# Motor_Controller.net
KiCad netlist of a schematic drawn in EAGLE
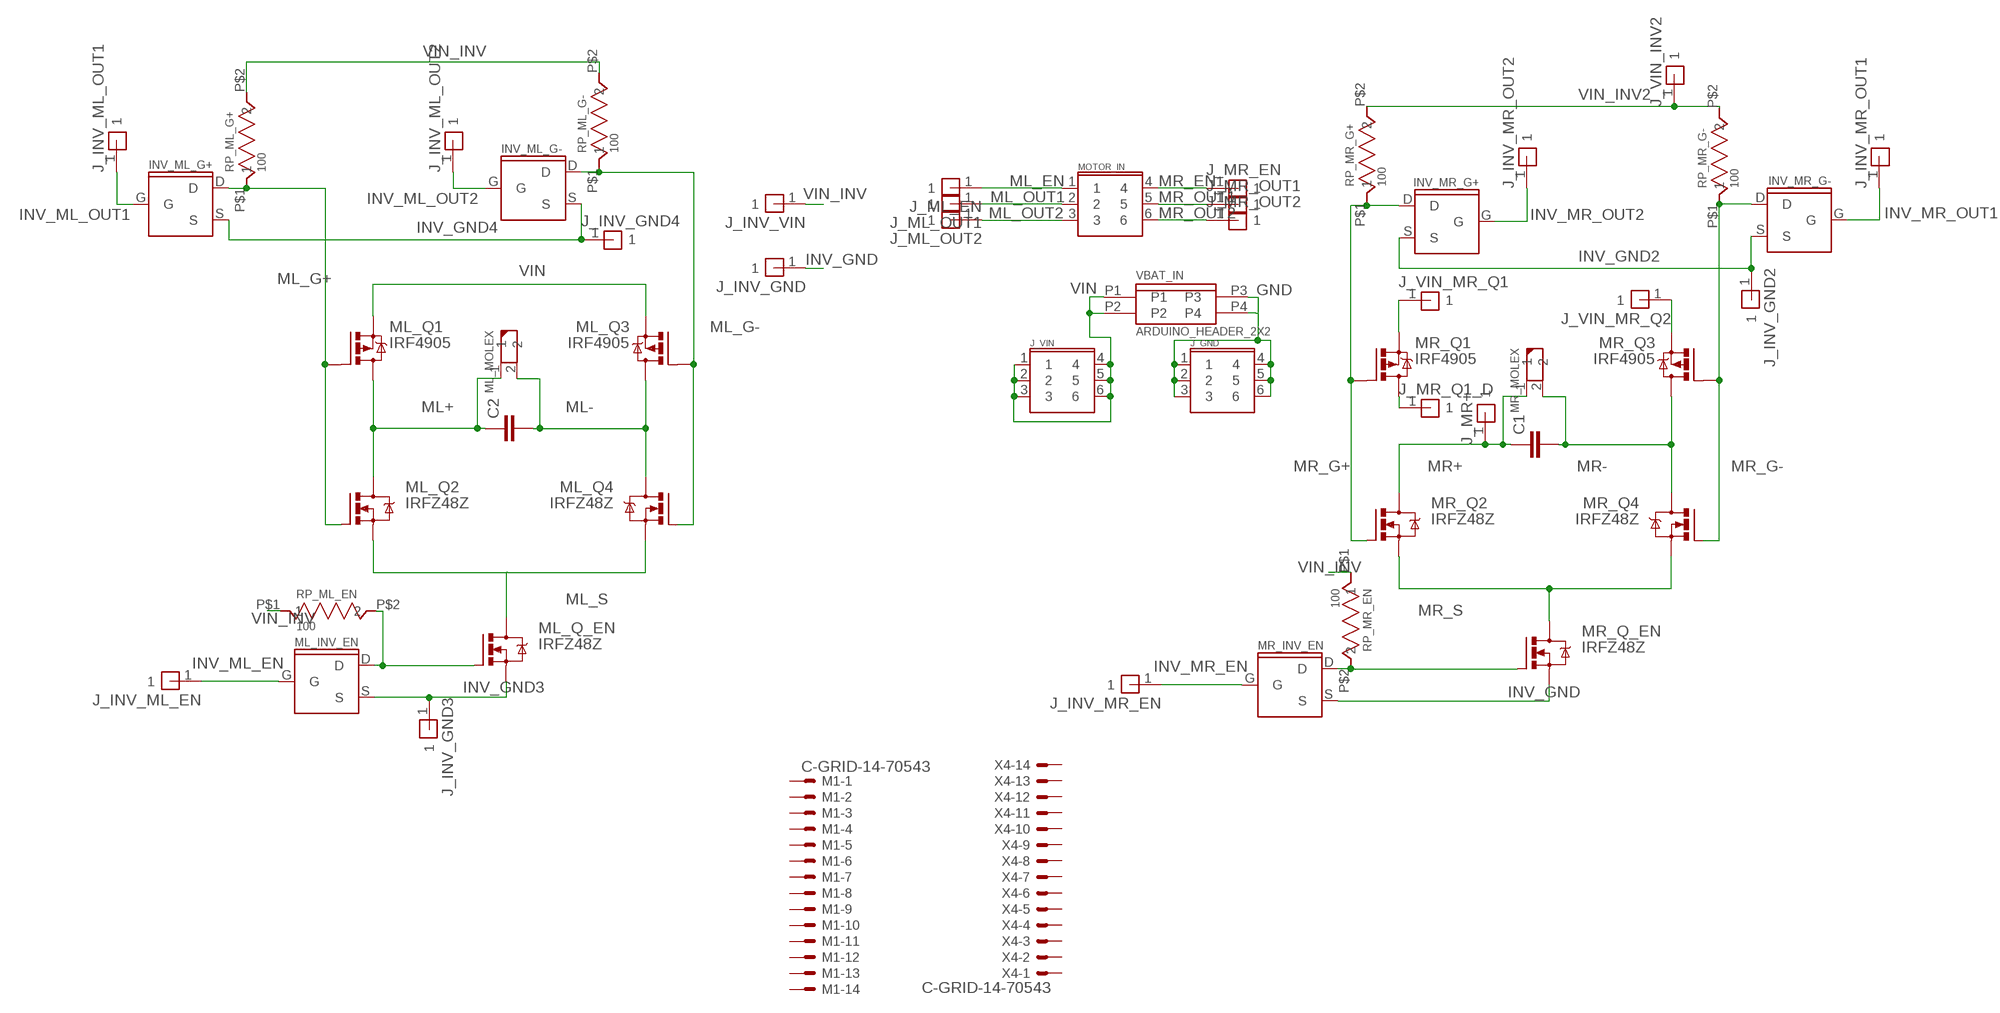
[diagram p0: schematic, sheet 1]

(export (version "E")
  (design (tool "Eeschema 10.0.6"))
  (components
    (comp (ref "C1")
      (value "C5/3")
      (footprint "eagle-import:C5B3")
      (libsource (lib "eagle-import") (part "C5/3"))
    )
    (comp (ref "C2")
      (value "C5/3")
      (footprint "eagle-import:C5B3")
      (libsource (lib "eagle-import") (part "C5/3"))
    )
    (comp (ref "INV_ML_G+")
      (value "2N7000")
      (footprint "eagle-import:TO-92")
      (libsource (lib "eagle-import") (part "2N7000"))
    )
    (comp (ref "INV_ML_G-")
      (value "2N7000")
      (footprint "eagle-import:TO-92")
      (libsource (lib "eagle-import") (part "2N7000"))
    )
    (comp (ref "INV_MR_G+")
      (value "2N7000")
      (footprint "eagle-import:TO-92")
      (libsource (lib "eagle-import") (part "2N7000"))
    )
    (comp (ref "INV_MR_G-")
      (value "2N7000")
      (footprint "eagle-import:TO-92")
      (libsource (lib "eagle-import") (part "2N7000"))
    )
    (comp (ref "J_GND")
      (value "ARDUINO_HEADER_3X2")
      (footprint "eagle-import:ARDUINO_HEADER_3X2")
      (libsource (lib "eagle-import") (part "ARDUINO_HEADER_3X2"))
    )
    (comp (ref "J_INV_GND")
      (value "ARDUINO_HEADER_1X1_OCTAGON")
      (footprint "eagle-import:ARDUINO_HEADER_1X1_OCTAGON")
      (libsource (lib "eagle-import") (part "ARDUINO_HEADER_1X1_OCTAGON"))
    )
    (comp (ref "J_INV_GND2")
      (value "ARDUINO_HEADER_1X1_OCTAGON")
      (footprint "eagle-import:ARDUINO_HEADER_1X1_OCTAGON")
      (libsource (lib "eagle-import") (part "ARDUINO_HEADER_1X1_OCTAGON"))
    )
    (comp (ref "J_INV_GND3")
      (value "ARDUINO_HEADER_1X1_OCTAGON")
      (footprint "eagle-import:ARDUINO_HEADER_1X1_OCTAGON")
      (libsource (lib "eagle-import") (part "ARDUINO_HEADER_1X1_OCTAGON"))
    )
    (comp (ref "J_INV_GND4")
      (value "ARDUINO_HEADER_1X1_OCTAGON")
      (footprint "eagle-import:ARDUINO_HEADER_1X1_OCTAGON")
      (libsource (lib "eagle-import") (part "ARDUINO_HEADER_1X1_OCTAGON"))
    )
    (comp (ref "J_INV_ML_EN")
      (value "ARDUINO_HEADER_1X1_OCTAGON")
      (footprint "eagle-import:ARDUINO_HEADER_1X1_OCTAGON")
      (libsource (lib "eagle-import") (part "ARDUINO_HEADER_1X1_OCTAGON"))
    )
    (comp (ref "J_INV_ML_OUT1")
      (value "ARDUINO_HEADER_1X1_OCTAGON")
      (footprint "eagle-import:ARDUINO_HEADER_1X1_OCTAGON")
      (libsource (lib "eagle-import") (part "ARDUINO_HEADER_1X1_OCTAGON"))
    )
    (comp (ref "J_INV_ML_OUT2")
      (value "ARDUINO_HEADER_1X1_OCTAGON")
      (footprint "eagle-import:ARDUINO_HEADER_1X1_OCTAGON")
      (libsource (lib "eagle-import") (part "ARDUINO_HEADER_1X1_OCTAGON"))
    )
    (comp (ref "J_INV_MR_EN")
      (value "ARDUINO_HEADER_1X1_OCTAGON")
      (footprint "eagle-import:ARDUINO_HEADER_1X1_OCTAGON")
      (libsource (lib "eagle-import") (part "ARDUINO_HEADER_1X1_OCTAGON"))
    )
    (comp (ref "J_INV_MR_OUT1")
      (value "ARDUINO_HEADER_1X1_OCTAGON")
      (footprint "eagle-import:ARDUINO_HEADER_1X1_OCTAGON")
      (libsource (lib "eagle-import") (part "ARDUINO_HEADER_1X1_OCTAGON"))
    )
    (comp (ref "J_INV_MR_OUT2")
      (value "ARDUINO_HEADER_1X1_OCTAGON")
      (footprint "eagle-import:ARDUINO_HEADER_1X1_OCTAGON")
      (libsource (lib "eagle-import") (part "ARDUINO_HEADER_1X1_OCTAGON"))
    )
    (comp (ref "J_INV_VIN")
      (value "ARDUINO_HEADER_1X1_OCTAGON")
      (footprint "eagle-import:ARDUINO_HEADER_1X1_OCTAGON")
      (libsource (lib "eagle-import") (part "ARDUINO_HEADER_1X1_OCTAGON"))
    )
    (comp (ref "J_ML_EN")
      (value "ARDUINO_HEADER_1X1_OCTAGON")
      (footprint "eagle-import:ARDUINO_HEADER_1X1_OCTAGON")
      (libsource (lib "eagle-import") (part "ARDUINO_HEADER_1X1_OCTAGON"))
    )
    (comp (ref "J_ML_OUT1")
      (value "ARDUINO_HEADER_1X1_OCTAGON")
      (footprint "eagle-import:ARDUINO_HEADER_1X1_OCTAGON")
      (libsource (lib "eagle-import") (part "ARDUINO_HEADER_1X1_OCTAGON"))
    )
    (comp (ref "J_ML_OUT2")
      (value "ARDUINO_HEADER_1X1_OCTAGON")
      (footprint "eagle-import:ARDUINO_HEADER_1X1_OCTAGON")
      (libsource (lib "eagle-import") (part "ARDUINO_HEADER_1X1_OCTAGON"))
    )
    (comp (ref "J_MR+")
      (value "ARDUINO_HEADER_1X1_OCTAGON")
      (footprint "eagle-import:ARDUINO_HEADER_1X1_OCTAGON")
      (libsource (lib "eagle-import") (part "ARDUINO_HEADER_1X1_OCTAGON"))
    )
    (comp (ref "J_MR_EN")
      (value "ARDUINO_HEADER_1X1_OCTAGON")
      (footprint "eagle-import:ARDUINO_HEADER_1X1_OCTAGON")
      (libsource (lib "eagle-import") (part "ARDUINO_HEADER_1X1_OCTAGON"))
    )
    (comp (ref "J_MR_OUT1")
      (value "ARDUINO_HEADER_1X1_OCTAGON")
      (footprint "eagle-import:ARDUINO_HEADER_1X1_OCTAGON")
      (libsource (lib "eagle-import") (part "ARDUINO_HEADER_1X1_OCTAGON"))
    )
    (comp (ref "J_MR_OUT2")
      (value "ARDUINO_HEADER_1X1_OCTAGON")
      (footprint "eagle-import:ARDUINO_HEADER_1X1_OCTAGON")
      (libsource (lib "eagle-import") (part "ARDUINO_HEADER_1X1_OCTAGON"))
    )
    (comp (ref "J_MR_Q1_D")
      (value "ARDUINO_HEADER_1X1_OCTAGON")
      (footprint "eagle-import:ARDUINO_HEADER_1X1_OCTAGON")
      (libsource (lib "eagle-import") (part "ARDUINO_HEADER_1X1_OCTAGON"))
    )
    (comp (ref "J_VIN")
      (value "ARDUINO_HEADER_3X2")
      (footprint "eagle-import:ARDUINO_HEADER_3X2")
      (libsource (lib "eagle-import") (part "ARDUINO_HEADER_3X2"))
    )
    (comp (ref "J_VIN_INV2")
      (value "ARDUINO_HEADER_1X1_OCTAGON")
      (footprint "eagle-import:ARDUINO_HEADER_1X1_OCTAGON")
      (libsource (lib "eagle-import") (part "ARDUINO_HEADER_1X1_OCTAGON"))
    )
    (comp (ref "J_VIN_MR_Q1")
      (value "ARDUINO_HEADER_1X1_OCTAGON")
      (footprint "eagle-import:ARDUINO_HEADER_1X1_OCTAGON")
      (libsource (lib "eagle-import") (part "ARDUINO_HEADER_1X1_OCTAGON"))
    )
    (comp (ref "J_VIN_MR_Q2")
      (value "ARDUINO_HEADER_1X1_OCTAGON")
      (footprint "eagle-import:ARDUINO_HEADER_1X1_OCTAGON")
      (libsource (lib "eagle-import") (part "ARDUINO_HEADER_1X1_OCTAGON"))
    )
    (comp (ref "M1")
      (value "C-GRID-14-70543")
      (footprint "eagle-import:70543-14")
      (libsource (lib "eagle-import") (part "C-GRID-14-70543"))
    )
    (comp (ref "ML_INV_EN")
      (value "2N7000")
      (footprint "eagle-import:TO-92")
      (libsource (lib "eagle-import") (part "2N7000"))
    )
    (comp (ref "ML_MOLEX")
      (value "MOLEX_2_PIN")
      (footprint "eagle-import:MOLEX_2_PIN")
      (libsource (lib "eagle-import") (part "MOLEX_2_PIN"))
    )
    (comp (ref "ML_Q1")
      (value "IRF4905")
      (footprint "eagle-import:TO220BH")
      (libsource (lib "eagle-import") (part "IRF4905"))
    )
    (comp (ref "ML_Q2")
      (value "IRFZ48Z")
      (footprint "eagle-import:TO220BH")
      (libsource (lib "eagle-import") (part "IRFZ48Z"))
    )
    (comp (ref "ML_Q3")
      (value "IRF4905")
      (footprint "eagle-import:TO220BH")
      (libsource (lib "eagle-import") (part "IRF4905"))
    )
    (comp (ref "ML_Q4")
      (value "IRFZ48Z")
      (footprint "eagle-import:TO220BH")
      (libsource (lib "eagle-import") (part "IRFZ48Z"))
    )
    (comp (ref "ML_Q_EN")
      (value "IRFZ48Z")
      (footprint "eagle-import:TO220BH")
      (libsource (lib "eagle-import") (part "IRFZ48Z"))
    )
    (comp (ref "MOTOR_IN")
      (value "ARDUINO_HEADER_3X2")
      (footprint "eagle-import:ARDUINO_HEADER_3X2")
      (libsource (lib "eagle-import") (part "ARDUINO_HEADER_3X2"))
    )
    (comp (ref "MR_INV_EN")
      (value "2N7000")
      (footprint "eagle-import:TO-92")
      (libsource (lib "eagle-import") (part "2N7000"))
    )
    (comp (ref "MR_MOLEX")
      (value "MOLEX_2_PIN")
      (footprint "eagle-import:MOLEX_2_PIN")
      (libsource (lib "eagle-import") (part "MOLEX_2_PIN"))
    )
    (comp (ref "MR_Q1")
      (value "IRF4905")
      (footprint "eagle-import:TO220BH")
      (libsource (lib "eagle-import") (part "IRF4905"))
    )
    (comp (ref "MR_Q2")
      (value "IRFZ48Z")
      (footprint "eagle-import:TO220BH")
      (libsource (lib "eagle-import") (part "IRFZ48Z"))
    )
    (comp (ref "MR_Q3")
      (value "IRF4905")
      (footprint "eagle-import:TO220BH")
      (libsource (lib "eagle-import") (part "IRF4905"))
    )
    (comp (ref "MR_Q4")
      (value "IRFZ48Z")
      (footprint "eagle-import:TO220BH")
      (libsource (lib "eagle-import") (part "IRFZ48Z"))
    )
    (comp (ref "MR_Q_EN")
      (value "IRFZ48Z")
      (footprint "eagle-import:TO220BH")
      (libsource (lib "eagle-import") (part "IRFZ48Z"))
    )
    (comp (ref "RP_ML_EN")
      (value "100")
      (footprint "eagle-import:RESISTOR_THROUGH_8MM")
      (libsource (lib "eagle-import") (part "RESISTOR_THROUGH_8MM"))
    )
    (comp (ref "RP_ML_G+")
      (value "100")
      (footprint "eagle-import:RESISTOR_THROUGH_8MM")
      (libsource (lib "eagle-import") (part "RESISTOR_THROUGH_8MM"))
    )
    (comp (ref "RP_ML_G-")
      (value "100")
      (footprint "eagle-import:RESISTOR_THROUGH_8MM")
      (libsource (lib "eagle-import") (part "RESISTOR_THROUGH_8MM"))
    )
    (comp (ref "RP_MR_EN")
      (value "100")
      (footprint "eagle-import:RESISTOR_THROUGH_8MM")
      (libsource (lib "eagle-import") (part "RESISTOR_THROUGH_8MM"))
    )
    (comp (ref "RP_MR_G+")
      (value "100")
      (footprint "eagle-import:RESISTOR_THROUGH_8MM")
      (libsource (lib "eagle-import") (part "RESISTOR_THROUGH_8MM"))
    )
    (comp (ref "RP_MR_G-")
      (value "100")
      (footprint "eagle-import:RESISTOR_THROUGH_8MM")
      (libsource (lib "eagle-import") (part "RESISTOR_THROUGH_8MM"))
    )
    (comp (ref "VBAT_IN")
      (value "ARDUINO_HEADER_2X2")
      (footprint "eagle-import:ARDUINO_HEADER_2X2")
      (libsource (lib "eagle-import") (part "ARDUINO_HEADER_2X2"))
    )
    (comp (ref "X4")
      (value "C-GRID-14-70543")
      (footprint "eagle-import:70543-14")
      (libsource (lib "eagle-import") (part "C-GRID-14-70543"))
    )
  )
  (nets
    (net (code "1") (name "/GND") (class "Default")
      (node (ref "J_GND") (pin "1") (pinfunction "1_1") (pintype "bidirectional"))
      (node (ref "J_GND") (pin "2") (pinfunction "2_2") (pintype "bidirectional"))
      (node (ref "J_GND") (pin "3") (pinfunction "3_3") (pintype "bidirectional"))
      (node (ref "J_GND") (pin "4") (pinfunction "4_4") (pintype "bidirectional"))
      (node (ref "J_GND") (pin "5") (pinfunction "5_5") (pintype "bidirectional"))
      (node (ref "J_GND") (pin "6") (pinfunction "6_6") (pintype "bidirectional"))
      (node (ref "VBAT_IN") (pin "P3") (pinfunction "P3_P3") (pintype "bidirectional"))
      (node (ref "VBAT_IN") (pin "P4") (pinfunction "P4_P4") (pintype "bidirectional"))
    )
    (net (code "2") (name "/INV_GND") (class "Default")
      (node (ref "J_INV_GND") (pin "1") (pinfunction "1_1") (pintype "bidirectional"))
      (node (ref "MR_INV_EN") (pin "S") (pinfunction "S_S") (pintype "bidirectional"))
      (node (ref "MR_Q_EN") (pin "S") (pinfunction "S_S") (pintype "passive"))
    )
    (net (code "3") (name "/INV_GND2") (class "Default")
      (node (ref "INV_MR_G+") (pin "S") (pinfunction "S_S") (pintype "bidirectional"))
      (node (ref "INV_MR_G-") (pin "S") (pinfunction "S_S") (pintype "bidirectional"))
      (node (ref "J_INV_GND2") (pin "1") (pinfunction "1_1") (pintype "bidirectional"))
    )
    (net (code "4") (name "/INV_GND3") (class "Default")
      (node (ref "J_INV_GND3") (pin "1") (pinfunction "1_1") (pintype "bidirectional"))
      (node (ref "ML_INV_EN") (pin "S") (pinfunction "S_S") (pintype "bidirectional"))
      (node (ref "ML_Q_EN") (pin "S") (pinfunction "S_S") (pintype "passive"))
    )
    (net (code "5") (name "/INV_GND4") (class "Default")
      (node (ref "INV_ML_G+") (pin "S") (pinfunction "S_S") (pintype "bidirectional"))
      (node (ref "INV_ML_G-") (pin "S") (pinfunction "S_S") (pintype "bidirectional"))
      (node (ref "J_INV_GND4") (pin "1") (pinfunction "1_1") (pintype "bidirectional"))
    )
    (net (code "6") (name "/INV_ML_EN") (class "Default")
      (node (ref "J_INV_ML_EN") (pin "1") (pinfunction "1_1") (pintype "bidirectional"))
      (node (ref "ML_INV_EN") (pin "G") (pinfunction "G_G") (pintype "bidirectional"))
    )
    (net (code "7") (name "/INV_ML_OUT1") (class "Default")
      (node (ref "INV_ML_G+") (pin "G") (pinfunction "G_G") (pintype "bidirectional"))
      (node (ref "J_INV_ML_OUT1") (pin "1") (pinfunction "1_1") (pintype "bidirectional"))
    )
    (net (code "8") (name "/INV_ML_OUT2") (class "Default")
      (node (ref "INV_ML_G-") (pin "G") (pinfunction "G_G") (pintype "bidirectional"))
      (node (ref "J_INV_ML_OUT2") (pin "1") (pinfunction "1_1") (pintype "bidirectional"))
    )
    (net (code "9") (name "/INV_MR_EN") (class "Default")
      (node (ref "J_INV_MR_EN") (pin "1") (pinfunction "1_1") (pintype "bidirectional"))
      (node (ref "MR_INV_EN") (pin "G") (pinfunction "G_G") (pintype "bidirectional"))
    )
    (net (code "10") (name "/INV_MR_OUT1") (class "Default")
      (node (ref "INV_MR_G-") (pin "G") (pinfunction "G_G") (pintype "bidirectional"))
      (node (ref "J_INV_MR_OUT1") (pin "1") (pinfunction "1_1") (pintype "bidirectional"))
    )
    (net (code "11") (name "/INV_MR_OUT2") (class "Default")
      (node (ref "INV_MR_G+") (pin "G") (pinfunction "G_G") (pintype "bidirectional"))
      (node (ref "J_INV_MR_OUT2") (pin "1") (pinfunction "1_1") (pintype "bidirectional"))
    )
    (net (code "12") (name "/ML+") (class "Default")
      (node (ref "C2") (pin "1") (pinfunction "1_1") (pintype "passive"))
      (node (ref "ML_MOLEX") (pin "1") (pinfunction "1_1") (pintype "bidirectional"))
      (node (ref "ML_Q1") (pin "D") (pinfunction "D_D") (pintype "passive"))
      (node (ref "ML_Q2") (pin "D") (pinfunction "D_D") (pintype "passive"))
    )
    (net (code "13") (name "/ML-") (class "Default")
      (node (ref "C2") (pin "2") (pinfunction "2_2") (pintype "passive"))
      (node (ref "ML_MOLEX") (pin "2") (pinfunction "2_2") (pintype "bidirectional"))
      (node (ref "ML_Q3") (pin "D") (pinfunction "D_D") (pintype "passive"))
      (node (ref "ML_Q4") (pin "D") (pinfunction "D_D") (pintype "passive"))
    )
    (net (code "14") (name "/ML_EN") (class "Default")
      (node (ref "J_ML_EN") (pin "1") (pinfunction "1_1") (pintype "bidirectional"))
      (node (ref "MOTOR_IN") (pin "1") (pinfunction "1_1") (pintype "bidirectional"))
    )
    (net (code "15") (name "/ML_G+") (class "Default")
      (node (ref "INV_ML_G+") (pin "D") (pinfunction "D_D") (pintype "bidirectional"))
      (node (ref "ML_Q1") (pin "G") (pinfunction "G_G") (pintype "passive"))
      (node (ref "ML_Q2") (pin "G") (pinfunction "G_G") (pintype "passive"))
      (node (ref "RP_ML_G+") (pin "P$1") (pinfunction "1_P$1") (pintype "bidirectional"))
    )
    (net (code "16") (name "/ML_G-") (class "Default")
      (node (ref "INV_ML_G-") (pin "D") (pinfunction "D_D") (pintype "bidirectional"))
      (node (ref "ML_Q3") (pin "G") (pinfunction "G_G") (pintype "passive"))
      (node (ref "ML_Q4") (pin "G") (pinfunction "G_G") (pintype "passive"))
      (node (ref "RP_ML_G-") (pin "P$1") (pinfunction "1_P$1") (pintype "bidirectional"))
    )
    (net (code "17") (name "/ML_OUT1") (class "Default")
      (node (ref "J_ML_OUT1") (pin "1") (pinfunction "1_1") (pintype "bidirectional"))
      (node (ref "MOTOR_IN") (pin "2") (pinfunction "2_2") (pintype "bidirectional"))
    )
    (net (code "18") (name "/ML_OUT2") (class "Default")
      (node (ref "J_ML_OUT2") (pin "1") (pinfunction "1_1") (pintype "bidirectional"))
      (node (ref "MOTOR_IN") (pin "3") (pinfunction "3_3") (pintype "bidirectional"))
    )
    (net (code "19") (name "/ML_S") (class "Default")
      (node (ref "ML_Q2") (pin "S") (pinfunction "S_S") (pintype "passive"))
      (node (ref "ML_Q4") (pin "S") (pinfunction "S_S") (pintype "passive"))
      (node (ref "ML_Q_EN") (pin "D") (pinfunction "D_D") (pintype "passive"))
    )
    (net (code "20") (name "/MR+") (class "Default")
      (node (ref "C1") (pin "1") (pinfunction "1_1") (pintype "passive"))
      (node (ref "J_MR+") (pin "1") (pinfunction "1_1") (pintype "bidirectional"))
      (node (ref "MR_MOLEX") (pin "1") (pinfunction "1_1") (pintype "bidirectional"))
      (node (ref "MR_Q2") (pin "D") (pinfunction "D_D") (pintype "passive"))
    )
    (net (code "21") (name "/MR-") (class "Default")
      (node (ref "C1") (pin "2") (pinfunction "2_2") (pintype "passive"))
      (node (ref "MR_MOLEX") (pin "2") (pinfunction "2_2") (pintype "bidirectional"))
      (node (ref "MR_Q3") (pin "D") (pinfunction "D_D") (pintype "passive"))
      (node (ref "MR_Q4") (pin "D") (pinfunction "D_D") (pintype "passive"))
    )
    (net (code "22") (name "/MR_EN") (class "Default")
      (node (ref "J_MR_EN") (pin "1") (pinfunction "1_1") (pintype "bidirectional"))
      (node (ref "MOTOR_IN") (pin "4") (pinfunction "4_4") (pintype "bidirectional"))
    )
    (net (code "23") (name "/MR_G+") (class "Default")
      (node (ref "INV_MR_G+") (pin "D") (pinfunction "D_D") (pintype "bidirectional"))
      (node (ref "MR_Q1") (pin "G") (pinfunction "G_G") (pintype "passive"))
      (node (ref "MR_Q2") (pin "G") (pinfunction "G_G") (pintype "passive"))
      (node (ref "RP_MR_G+") (pin "P$1") (pinfunction "1_P$1") (pintype "bidirectional"))
    )
    (net (code "24") (name "/MR_G-") (class "Default")
      (node (ref "INV_MR_G-") (pin "D") (pinfunction "D_D") (pintype "bidirectional"))
      (node (ref "MR_Q3") (pin "G") (pinfunction "G_G") (pintype "passive"))
      (node (ref "MR_Q4") (pin "G") (pinfunction "G_G") (pintype "passive"))
      (node (ref "RP_MR_G-") (pin "P$1") (pinfunction "1_P$1") (pintype "bidirectional"))
    )
    (net (code "25") (name "/MR_OUT1") (class "Default")
      (node (ref "J_MR_OUT1") (pin "1") (pinfunction "1_1") (pintype "bidirectional"))
      (node (ref "MOTOR_IN") (pin "5") (pinfunction "5_5") (pintype "bidirectional"))
    )
    (net (code "26") (name "/MR_OUT2") (class "Default")
      (node (ref "J_MR_OUT2") (pin "1") (pinfunction "1_1") (pintype "bidirectional"))
      (node (ref "MOTOR_IN") (pin "6") (pinfunction "6_6") (pintype "bidirectional"))
    )
    (net (code "27") (name "/MR_S") (class "Default")
      (node (ref "MR_Q2") (pin "S") (pinfunction "S_S") (pintype "passive"))
      (node (ref "MR_Q4") (pin "S") (pinfunction "S_S") (pintype "passive"))
      (node (ref "MR_Q_EN") (pin "D") (pinfunction "D_D") (pintype "passive"))
    )
    (net (code "28") (name "/VIN") (class "Default")
      (node (ref "J_VIN") (pin "1") (pinfunction "1_1") (pintype "bidirectional"))
      (node (ref "J_VIN") (pin "2") (pinfunction "2_2") (pintype "bidirectional"))
      (node (ref "J_VIN") (pin "3") (pinfunction "3_3") (pintype "bidirectional"))
      (node (ref "J_VIN") (pin "4") (pinfunction "4_4") (pintype "bidirectional"))
      (node (ref "J_VIN") (pin "5") (pinfunction "5_5") (pintype "bidirectional"))
      (node (ref "J_VIN") (pin "6") (pinfunction "6_6") (pintype "bidirectional"))
      (node (ref "ML_Q1") (pin "S") (pinfunction "S_S") (pintype "passive"))
      (node (ref "ML_Q3") (pin "S") (pinfunction "S_S") (pintype "passive"))
      (node (ref "VBAT_IN") (pin "P1") (pinfunction "P1_P1") (pintype "bidirectional"))
      (node (ref "VBAT_IN") (pin "P2") (pinfunction "P2_P2") (pintype "bidirectional"))
    )
    (net (code "29") (name "/VIN_INV") (class "Default")
      (node (ref "J_INV_VIN") (pin "1") (pinfunction "1_1") (pintype "bidirectional"))
      (node (ref "RP_ML_EN") (pin "P$1") (pinfunction "1_P$1") (pintype "bidirectional"))
      (node (ref "RP_ML_G+") (pin "P$2") (pinfunction "2_P$2") (pintype "bidirectional"))
      (node (ref "RP_ML_G-") (pin "P$2") (pinfunction "2_P$2") (pintype "bidirectional"))
      (node (ref "RP_MR_EN") (pin "P$1") (pinfunction "1_P$1") (pintype "bidirectional"))
    )
    (net (code "30") (name "/VIN_INV2") (class "Default")
      (node (ref "J_VIN_INV2") (pin "1") (pinfunction "1_1") (pintype "bidirectional"))
      (node (ref "RP_MR_G+") (pin "P$2") (pinfunction "2_P$2") (pintype "bidirectional"))
      (node (ref "RP_MR_G-") (pin "P$2") (pinfunction "2_P$2") (pintype "bidirectional"))
    )
    (net (code "31") (name "Net-(J_MR_Q1_D-Pad1)") (class "Default")
      (node (ref "J_MR_Q1_D") (pin "1") (pinfunction "1_1") (pintype "bidirectional"))
      (node (ref "MR_Q1") (pin "D") (pinfunction "D_D") (pintype "passive"))
    )
    (net (code "32") (name "Net-(J_VIN_MR_Q1-Pad1)") (class "Default")
      (node (ref "J_VIN_MR_Q1") (pin "1") (pinfunction "1_1") (pintype "bidirectional"))
      (node (ref "MR_Q1") (pin "S") (pinfunction "S_S") (pintype "passive"))
    )
    (net (code "33") (name "Net-(J_VIN_MR_Q2-Pad1)") (class "Default")
      (node (ref "J_VIN_MR_Q2") (pin "1") (pinfunction "1_1") (pintype "bidirectional"))
      (node (ref "MR_Q3") (pin "S") (pinfunction "S_S") (pintype "passive"))
    )
    (net (code "34") (name "Net-(RP_ML_EN-2)") (class "Default")
      (node (ref "ML_INV_EN") (pin "D") (pinfunction "D_D") (pintype "bidirectional"))
      (node (ref "ML_Q_EN") (pin "G") (pinfunction "G_G") (pintype "passive"))
      (node (ref "RP_ML_EN") (pin "P$2") (pinfunction "2_P$2") (pintype "bidirectional"))
    )
    (net (code "35") (name "Net-(RP_MR_EN-2)") (class "Default")
      (node (ref "MR_INV_EN") (pin "D") (pinfunction "D_D") (pintype "bidirectional"))
      (node (ref "MR_Q_EN") (pin "G") (pinfunction "G_G") (pintype "passive"))
      (node (ref "RP_MR_EN") (pin "P$2") (pinfunction "2_P$2") (pintype "bidirectional"))
    )
    (net (code "36") (name "unconnected-(M1A-S-Pad1)") (class "Default")
      (node (ref "M1") (pin "1") (pinfunction "S_1") (pintype "passive"))
    )
    (net (code "37") (name "unconnected-(M1B-S-Pad10)") (class "Default")
      (node (ref "M1") (pin "10") (pinfunction "S_10") (pintype "passive"))
    )
    (net (code "38") (name "unconnected-(M1C-S-Pad11)") (class "Default")
      (node (ref "M1") (pin "11") (pinfunction "S_11") (pintype "passive"))
    )
    (net (code "39") (name "unconnected-(M1D-S-Pad12)") (class "Default")
      (node (ref "M1") (pin "12") (pinfunction "S_12") (pintype "passive"))
    )
    (net (code "40") (name "unconnected-(M1E-S-Pad13)") (class "Default")
      (node (ref "M1") (pin "13") (pinfunction "S_13") (pintype "passive"))
    )
    (net (code "41") (name "unconnected-(M1F-S-Pad14)") (class "Default")
      (node (ref "M1") (pin "14") (pinfunction "S_14") (pintype "passive"))
    )
    (net (code "42") (name "unconnected-(M1G-S-Pad2)") (class "Default")
      (node (ref "M1") (pin "2") (pinfunction "S_2") (pintype "passive"))
    )
    (net (code "43") (name "unconnected-(M1H-S-Pad3)") (class "Default")
      (node (ref "M1") (pin "3") (pinfunction "S_3") (pintype "passive"))
    )
    (net (code "44") (name "unconnected-(M1I-S-Pad4)") (class "Default")
      (node (ref "M1") (pin "4") (pinfunction "S_4") (pintype "passive"))
    )
    (net (code "45") (name "unconnected-(M1J-S-Pad5)") (class "Default")
      (node (ref "M1") (pin "5") (pinfunction "S_5") (pintype "passive"))
    )
    (net (code "46") (name "unconnected-(M1K-S-Pad6)") (class "Default")
      (node (ref "M1") (pin "6") (pinfunction "S_6") (pintype "passive"))
    )
    (net (code "47") (name "unconnected-(M1L-S-Pad7)") (class "Default")
      (node (ref "M1") (pin "7") (pinfunction "S_7") (pintype "passive"))
    )
    (net (code "48") (name "unconnected-(M1M-S-Pad8)") (class "Default")
      (node (ref "M1") (pin "8") (pinfunction "S_8") (pintype "passive"))
    )
    (net (code "49") (name "unconnected-(M1N-S-Pad9)") (class "Default")
      (node (ref "M1") (pin "9") (pinfunction "S_9") (pintype "passive"))
    )
    (net (code "50") (name "unconnected-(X4A-S-Pad1)") (class "Default")
      (node (ref "X4") (pin "1") (pinfunction "S_1") (pintype "passive"))
    )
    (net (code "51") (name "unconnected-(X4B-S-Pad10)") (class "Default")
      (node (ref "X4") (pin "10") (pinfunction "S_10") (pintype "passive"))
    )
    (net (code "52") (name "unconnected-(X4C-S-Pad11)") (class "Default")
      (node (ref "X4") (pin "11") (pinfunction "S_11") (pintype "passive"))
    )
    (net (code "53") (name "unconnected-(X4D-S-Pad12)") (class "Default")
      (node (ref "X4") (pin "12") (pinfunction "S_12") (pintype "passive"))
    )
    (net (code "54") (name "unconnected-(X4E-S-Pad13)") (class "Default")
      (node (ref "X4") (pin "13") (pinfunction "S_13") (pintype "passive"))
    )
    (net (code "55") (name "unconnected-(X4F-S-Pad14)") (class "Default")
      (node (ref "X4") (pin "14") (pinfunction "S_14") (pintype "passive"))
    )
    (net (code "56") (name "unconnected-(X4G-S-Pad2)") (class "Default")
      (node (ref "X4") (pin "2") (pinfunction "S_2") (pintype "passive"))
    )
    (net (code "57") (name "unconnected-(X4H-S-Pad3)") (class "Default")
      (node (ref "X4") (pin "3") (pinfunction "S_3") (pintype "passive"))
    )
    (net (code "58") (name "unconnected-(X4I-S-Pad4)") (class "Default")
      (node (ref "X4") (pin "4") (pinfunction "S_4") (pintype "passive"))
    )
    (net (code "59") (name "unconnected-(X4J-S-Pad5)") (class "Default")
      (node (ref "X4") (pin "5") (pinfunction "S_5") (pintype "passive"))
    )
    (net (code "60") (name "unconnected-(X4K-S-Pad6)") (class "Default")
      (node (ref "X4") (pin "6") (pinfunction "S_6") (pintype "passive"))
    )
    (net (code "61") (name "unconnected-(X4L-S-Pad7)") (class "Default")
      (node (ref "X4") (pin "7") (pinfunction "S_7") (pintype "passive"))
    )
    (net (code "62") (name "unconnected-(X4M-S-Pad8)") (class "Default")
      (node (ref "X4") (pin "8") (pinfunction "S_8") (pintype "passive"))
    )
    (net (code "63") (name "unconnected-(X4N-S-Pad9)") (class "Default")
      (node (ref "X4") (pin "9") (pinfunction "S_9") (pintype "passive"))
    )
  )
)
